# piezo-driver_v0_3-R001.net
KiCad netlist of a schematic drawn in EAGLE
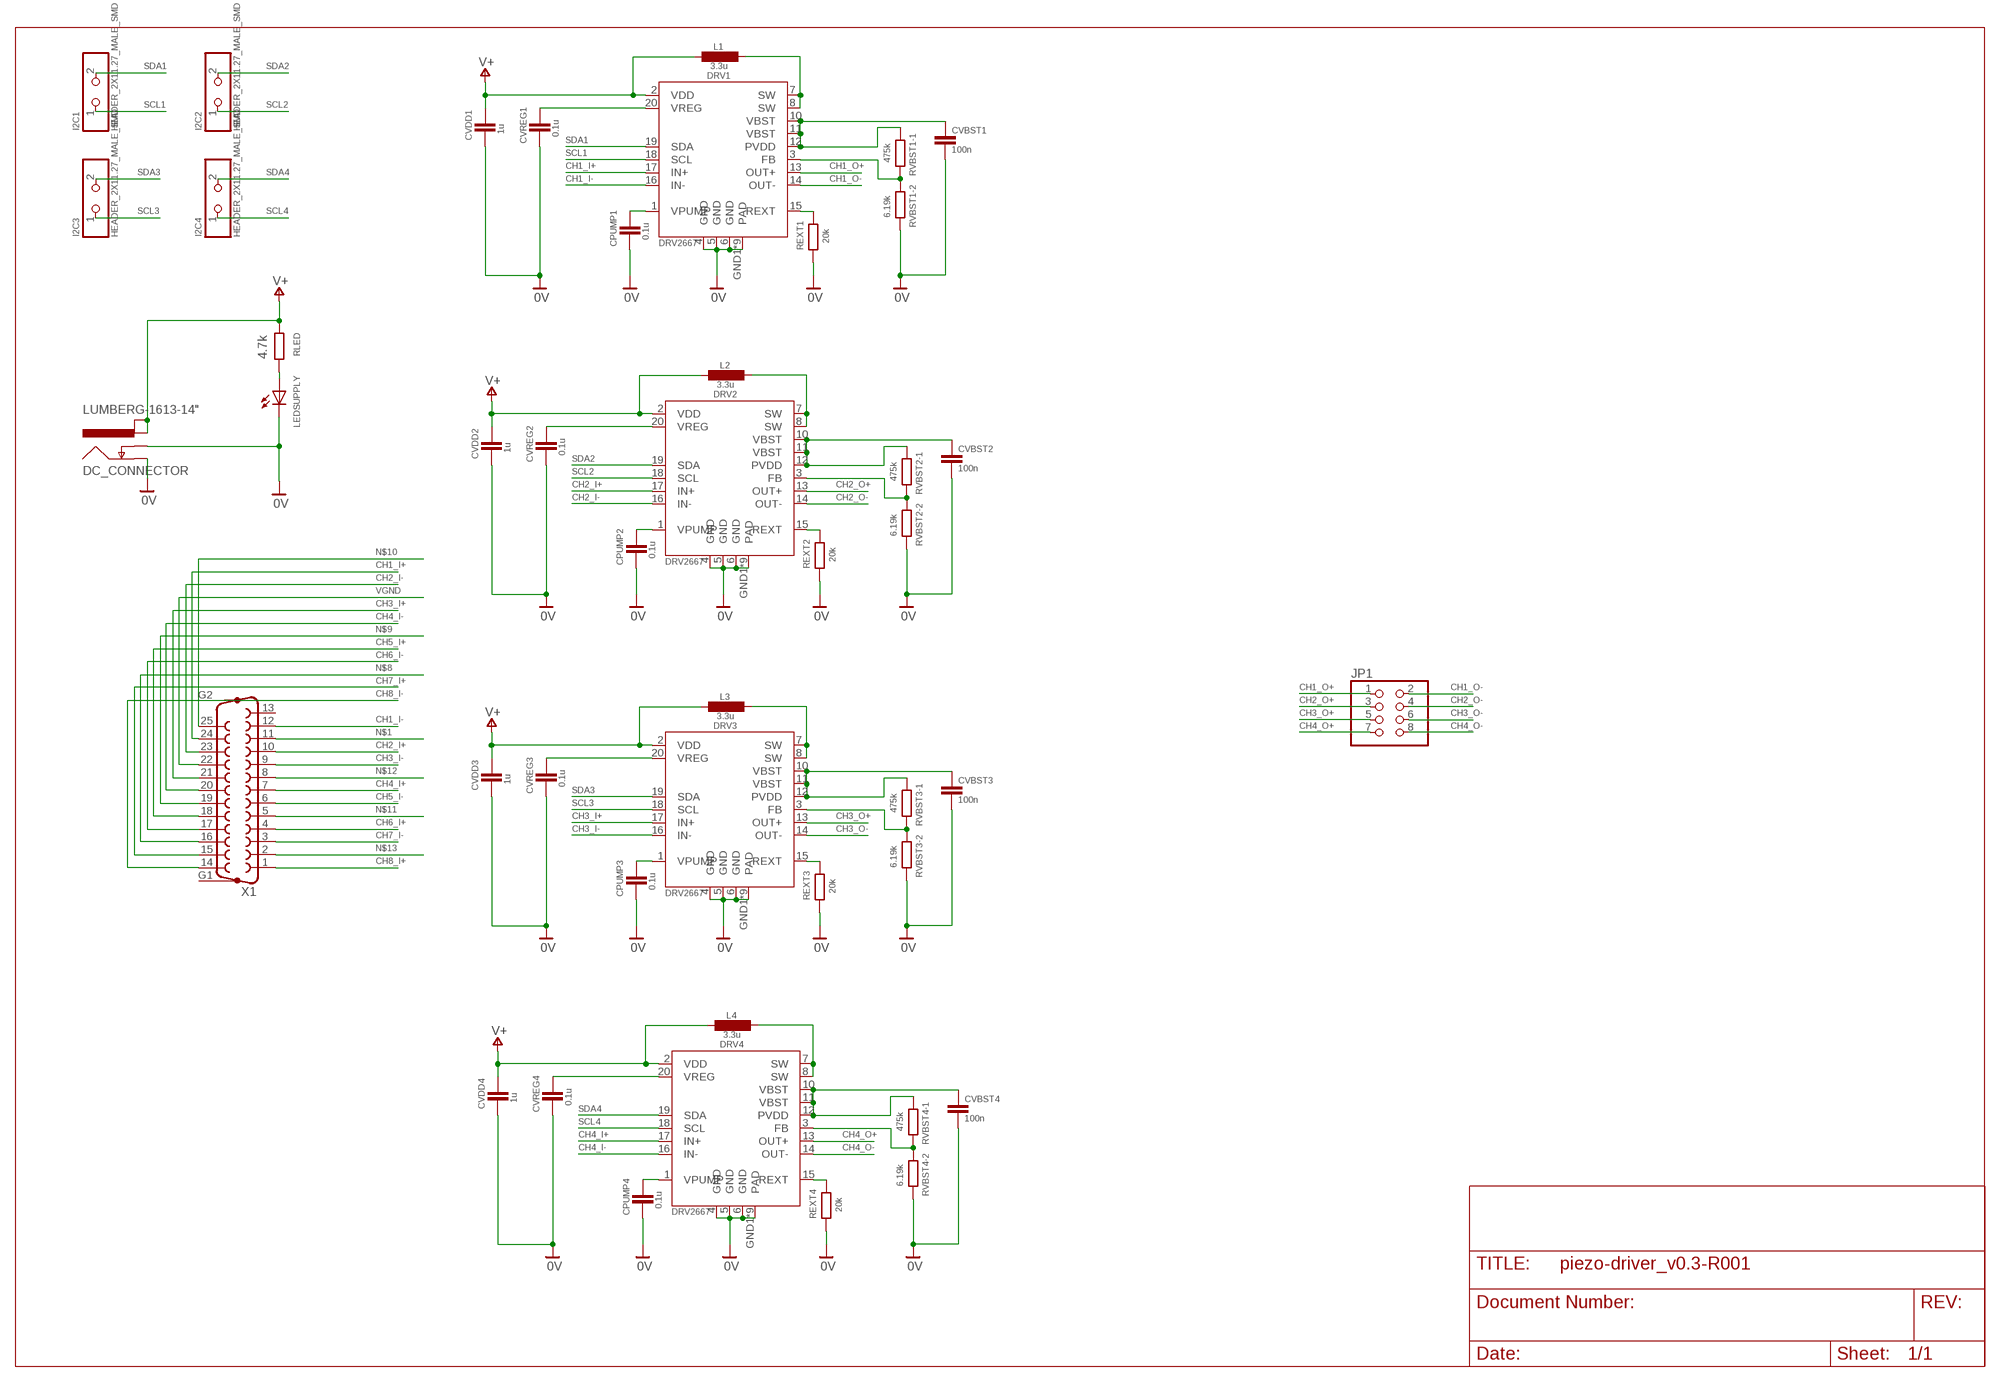
[diagram p0: schematic, sheet 1]

(export (version "E")
  (design (tool "Eeschema 10.0.6"))
  (components
    (comp (ref "CPUMP1")
      (value "0.1u")
      (footprint "eagle-import:C0805")
      (libsource (lib "eagle-import") (part "C-EUC0805"))
    )
    (comp (ref "CPUMP2")
      (value "0.1u")
      (footprint "eagle-import:C0805")
      (libsource (lib "eagle-import") (part "C-EUC0805"))
    )
    (comp (ref "CPUMP3")
      (value "0.1u")
      (footprint "eagle-import:C0805")
      (libsource (lib "eagle-import") (part "C-EUC0805"))
    )
    (comp (ref "CPUMP4")
      (value "0.1u")
      (footprint "eagle-import:C0805")
      (libsource (lib "eagle-import") (part "C-EUC0805"))
    )
    (comp (ref "CVBST1")
      (value "100n")
      (footprint "eagle-import:C0805")
      (libsource (lib "eagle-import") (part "C-EUC0805"))
    )
    (comp (ref "CVBST2")
      (value "100n")
      (footprint "eagle-import:C0805")
      (libsource (lib "eagle-import") (part "C-EUC0805"))
    )
    (comp (ref "CVBST3")
      (value "100n")
      (footprint "eagle-import:C0805")
      (libsource (lib "eagle-import") (part "C-EUC0805"))
    )
    (comp (ref "CVBST4")
      (value "100n")
      (footprint "eagle-import:C0805")
      (libsource (lib "eagle-import") (part "C-EUC0805"))
    )
    (comp (ref "CVDD1")
      (value "1u")
      (footprint "eagle-import:C0805")
      (libsource (lib "eagle-import") (part "C-EUC0805"))
    )
    (comp (ref "CVDD2")
      (value "1u")
      (footprint "eagle-import:C0805")
      (libsource (lib "eagle-import") (part "C-EUC0805"))
    )
    (comp (ref "CVDD3")
      (value "1u")
      (footprint "eagle-import:C0805")
      (libsource (lib "eagle-import") (part "C-EUC0805"))
    )
    (comp (ref "CVDD4")
      (value "1u")
      (footprint "eagle-import:C0805")
      (libsource (lib "eagle-import") (part "C-EUC0805"))
    )
    (comp (ref "CVREG1")
      (value "0.1u")
      (footprint "eagle-import:C0805")
      (libsource (lib "eagle-import") (part "C-EUC0805"))
    )
    (comp (ref "CVREG2")
      (value "0.1u")
      (footprint "eagle-import:C0805")
      (libsource (lib "eagle-import") (part "C-EUC0805"))
    )
    (comp (ref "CVREG3")
      (value "0.1u")
      (footprint "eagle-import:C0805")
      (libsource (lib "eagle-import") (part "C-EUC0805"))
    )
    (comp (ref "CVREG4")
      (value "0.1u")
      (footprint "eagle-import:C0805")
      (libsource (lib "eagle-import") (part "C-EUC0805"))
    )
    (comp (ref "DC_CONNECTOR")
      (value "LUMBERG-1613-14\"")
      (footprint "eagle-import:LUMBERG-1613_14")
      (libsource (lib "eagle-import") (part "LUMBERG-1613-14{dblquote}"))
    )
    (comp (ref "DRV1")
      (value "DRV2667QFN")
      (footprint "eagle-import:QFN400X400")
      (libsource (lib "eagle-import") (part "DRV2667QFN"))
    )
    (comp (ref "DRV2")
      (value "DRV2667QFN")
      (footprint "eagle-import:QFN400X400")
      (libsource (lib "eagle-import") (part "DRV2667QFN"))
    )
    (comp (ref "DRV3")
      (value "DRV2667QFN")
      (footprint "eagle-import:QFN400X400")
      (libsource (lib "eagle-import") (part "DRV2667QFN"))
    )
    (comp (ref "DRV4")
      (value "DRV2667QFN")
      (footprint "eagle-import:QFN400X400")
      (libsource (lib "eagle-import") (part "DRV2667QFN"))
    )
    (comp (ref "I2C1")
      (value "HEADER_2X11.27_MALE_SMD")
      (footprint "eagle-import:2X01_1.27_SMD")
      (libsource (lib "eagle-import") (part "HEADER_2X11.27_MALE_SMD"))
    )
    (comp (ref "I2C2")
      (value "HEADER_2X11.27_MALE_SMD")
      (footprint "eagle-import:2X01_1.27_SMD")
      (libsource (lib "eagle-import") (part "HEADER_2X11.27_MALE_SMD"))
    )
    (comp (ref "I2C3")
      (value "HEADER_2X11.27_MALE_SMD")
      (footprint "eagle-import:2X01_1.27_SMD")
      (libsource (lib "eagle-import") (part "HEADER_2X11.27_MALE_SMD"))
    )
    (comp (ref "I2C4")
      (value "HEADER_2X11.27_MALE_SMD")
      (footprint "eagle-import:2X01_1.27_SMD")
      (libsource (lib "eagle-import") (part "HEADER_2X11.27_MALE_SMD"))
    )
    (comp (ref "JP1")
      (value "PINHD-2X4/90")
      (footprint "eagle-import:2X04_90")
      (libsource (lib "eagle-import") (part "PINHD-2X4/90"))
    )
    (comp (ref "L1")
      (value "3.3u")
      (footprint "eagle-import:L3225M")
      (libsource (lib "eagle-import") (part "L-EUL3225M"))
    )
    (comp (ref "L2")
      (value "3.3u")
      (footprint "eagle-import:L3225M")
      (libsource (lib "eagle-import") (part "L-EUL3225M"))
    )
    (comp (ref "L3")
      (value "3.3u")
      (footprint "eagle-import:L3225M")
      (libsource (lib "eagle-import") (part "L-EUL3225M"))
    )
    (comp (ref "L4")
      (value "3.3u")
      (footprint "eagle-import:L3225M")
      (libsource (lib "eagle-import") (part "L-EUL3225M"))
    )
    (comp (ref "LEDSUPPLY")
      (value "LED0603")
      (footprint "eagle-import:LED-0603")
      (libsource (lib "eagle-import") (part "LED0603"))
    )
    (comp (ref "REXT1")
      (value "20k")
      (footprint "eagle-import:R0805")
      (libsource (lib "eagle-import") (part "R-EU_R0805"))
    )
    (comp (ref "REXT2")
      (value "20k")
      (footprint "eagle-import:R0805")
      (libsource (lib "eagle-import") (part "R-EU_R0805"))
    )
    (comp (ref "REXT3")
      (value "20k")
      (footprint "eagle-import:R0805")
      (libsource (lib "eagle-import") (part "R-EU_R0805"))
    )
    (comp (ref "REXT4")
      (value "20k")
      (footprint "eagle-import:R0805")
      (libsource (lib "eagle-import") (part "R-EU_R0805"))
    )
    (comp (ref "RLED")
      (value "4.7k")
      (footprint "eagle-import:R0805")
      (libsource (lib "eagle-import") (part "rcl_R-EU_R0805"))
    )
    (comp (ref "RVBST1-1")
      (value "475k")
      (footprint "eagle-import:R0805")
      (libsource (lib "eagle-import") (part "R-EU_R0805"))
    )
    (comp (ref "RVBST1-2")
      (value "6.19k")
      (footprint "eagle-import:R0805")
      (libsource (lib "eagle-import") (part "R-EU_R0805"))
    )
    (comp (ref "RVBST2-1")
      (value "475k")
      (footprint "eagle-import:R0805")
      (libsource (lib "eagle-import") (part "R-EU_R0805"))
    )
    (comp (ref "RVBST2-2")
      (value "6.19k")
      (footprint "eagle-import:R0805")
      (libsource (lib "eagle-import") (part "R-EU_R0805"))
    )
    (comp (ref "RVBST3-1")
      (value "475k")
      (footprint "eagle-import:R0805")
      (libsource (lib "eagle-import") (part "R-EU_R0805"))
    )
    (comp (ref "RVBST3-2")
      (value "6.19k")
      (footprint "eagle-import:R0805")
      (libsource (lib "eagle-import") (part "R-EU_R0805"))
    )
    (comp (ref "RVBST4-1")
      (value "475k")
      (footprint "eagle-import:R0805")
      (libsource (lib "eagle-import") (part "R-EU_R0805"))
    )
    (comp (ref "RVBST4-2")
      (value "6.19k")
      (footprint "eagle-import:R0805")
      (libsource (lib "eagle-import") (part "R-EU_R0805"))
    )
    (comp (ref "X1")
      (value "F25HP")
      (footprint "eagle-import:F25HP")
      (libsource (lib "eagle-import") (part "F25HP"))
    )
  )
  (nets
    (net (code "1") (name "/CH1_I+") (class "Default")
      (node (ref "DRV1") (pin "17") (pinfunction "IN+_17") (pintype "bidirectional"))
      (node (ref "X1") (pin "24") (pinfunction "24_24") (pintype "passive"))
    )
    (net (code "2") (name "/CH1_I-") (class "Default")
      (node (ref "DRV1") (pin "16") (pinfunction "IN-_16") (pintype "bidirectional"))
      (node (ref "X1") (pin "12") (pinfunction "12_12") (pintype "passive"))
    )
    (net (code "3") (name "/CH1_O+") (class "Default")
      (node (ref "DRV1") (pin "13") (pinfunction "OUT+_13") (pintype "bidirectional"))
      (node (ref "JP1") (pin "1") (pinfunction "1_1") (pintype "passive"))
    )
    (net (code "4") (name "/CH1_O-") (class "Default")
      (node (ref "DRV1") (pin "14") (pinfunction "OUT-_14") (pintype "bidirectional"))
      (node (ref "JP1") (pin "2") (pinfunction "2_2") (pintype "passive"))
    )
    (net (code "5") (name "/CH2_I+") (class "Default")
      (node (ref "DRV2") (pin "17") (pinfunction "IN+_17") (pintype "bidirectional"))
      (node (ref "X1") (pin "10") (pinfunction "10_10") (pintype "passive"))
    )
    (net (code "6") (name "/CH2_I-") (class "Default")
      (node (ref "DRV2") (pin "16") (pinfunction "IN-_16") (pintype "bidirectional"))
      (node (ref "X1") (pin "23") (pinfunction "23_23") (pintype "passive"))
    )
    (net (code "7") (name "/CH2_O+") (class "Default")
      (node (ref "DRV2") (pin "13") (pinfunction "OUT+_13") (pintype "bidirectional"))
      (node (ref "JP1") (pin "3") (pinfunction "3_3") (pintype "passive"))
    )
    (net (code "8") (name "/CH2_O-") (class "Default")
      (node (ref "DRV2") (pin "14") (pinfunction "OUT-_14") (pintype "bidirectional"))
      (node (ref "JP1") (pin "4") (pinfunction "4_4") (pintype "passive"))
    )
    (net (code "9") (name "/CH3_I+") (class "Default")
      (node (ref "DRV3") (pin "17") (pinfunction "IN+_17") (pintype "bidirectional"))
      (node (ref "X1") (pin "21") (pinfunction "21_21") (pintype "passive"))
    )
    (net (code "10") (name "/CH3_I-") (class "Default")
      (node (ref "DRV3") (pin "16") (pinfunction "IN-_16") (pintype "bidirectional"))
      (node (ref "X1") (pin "9") (pinfunction "9_9") (pintype "passive"))
    )
    (net (code "11") (name "/CH3_O+") (class "Default")
      (node (ref "DRV3") (pin "13") (pinfunction "OUT+_13") (pintype "bidirectional"))
      (node (ref "JP1") (pin "5") (pinfunction "5_5") (pintype "passive"))
    )
    (net (code "12") (name "/CH3_O-") (class "Default")
      (node (ref "DRV3") (pin "14") (pinfunction "OUT-_14") (pintype "bidirectional"))
      (node (ref "JP1") (pin "6") (pinfunction "6_6") (pintype "passive"))
    )
    (net (code "13") (name "/CH4_I+") (class "Default")
      (node (ref "DRV4") (pin "17") (pinfunction "IN+_17") (pintype "bidirectional"))
      (node (ref "X1") (pin "7") (pinfunction "7_7") (pintype "passive"))
    )
    (net (code "14") (name "/CH4_I-") (class "Default")
      (node (ref "DRV4") (pin "16") (pinfunction "IN-_16") (pintype "bidirectional"))
      (node (ref "X1") (pin "20") (pinfunction "20_20") (pintype "passive"))
    )
    (net (code "15") (name "/CH4_O+") (class "Default")
      (node (ref "DRV4") (pin "13") (pinfunction "OUT+_13") (pintype "bidirectional"))
      (node (ref "JP1") (pin "7") (pinfunction "7_7") (pintype "passive"))
    )
    (net (code "16") (name "/CH4_O-") (class "Default")
      (node (ref "DRV4") (pin "14") (pinfunction "OUT-_14") (pintype "bidirectional"))
      (node (ref "JP1") (pin "8") (pinfunction "8_8") (pintype "passive"))
    )
    (net (code "17") (name "/CH5_I+") (class "Default")
      (node (ref "X1") (pin "18") (pinfunction "18_18") (pintype "passive"))
    )
    (net (code "18") (name "/CH5_I-") (class "Default")
      (node (ref "X1") (pin "6") (pinfunction "6_6") (pintype "passive"))
    )
    (net (code "19") (name "/CH6_I+") (class "Default")
      (node (ref "X1") (pin "4") (pinfunction "4_4") (pintype "passive"))
    )
    (net (code "20") (name "/CH6_I-") (class "Default")
      (node (ref "X1") (pin "17") (pinfunction "17_17") (pintype "passive"))
    )
    (net (code "21") (name "/CH7_I+") (class "Default")
      (node (ref "X1") (pin "15") (pinfunction "15_15") (pintype "passive"))
    )
    (net (code "22") (name "/CH7_I-") (class "Default")
      (node (ref "X1") (pin "3") (pinfunction "3_3") (pintype "passive"))
    )
    (net (code "23") (name "/CH8_I+") (class "Default")
      (node (ref "X1") (pin "1") (pinfunction "1_1") (pintype "passive"))
    )
    (net (code "24") (name "/CH8_I-") (class "Default")
      (node (ref "X1") (pin "14") (pinfunction "14_14") (pintype "passive"))
    )
    (net (code "25") (name "/N$1") (class "Default")
      (node (ref "X1") (pin "11") (pinfunction "11_11") (pintype "passive"))
    )
    (net (code "26") (name "/N$8") (class "Default")
      (node (ref "X1") (pin "16") (pinfunction "16_16") (pintype "passive"))
    )
    (net (code "27") (name "/N$9") (class "Default")
      (node (ref "X1") (pin "19") (pinfunction "19_19") (pintype "passive"))
    )
    (net (code "28") (name "/N$10") (class "Default")
      (node (ref "X1") (pin "25") (pinfunction "25_25") (pintype "passive"))
    )
    (net (code "29") (name "/N$11") (class "Default")
      (node (ref "X1") (pin "5") (pinfunction "5_5") (pintype "passive"))
    )
    (net (code "30") (name "/N$12") (class "Default")
      (node (ref "X1") (pin "8") (pinfunction "8_8") (pintype "passive"))
    )
    (net (code "31") (name "/N$13") (class "Default")
      (node (ref "X1") (pin "2") (pinfunction "2_2") (pintype "passive"))
    )
    (net (code "32") (name "/SCL1") (class "Default")
      (node (ref "DRV1") (pin "18") (pinfunction "SCL_18") (pintype "bidirectional"))
      (node (ref "I2C1") (pin "1") (pinfunction "1_1") (pintype "passive"))
    )
    (net (code "33") (name "/SCL2") (class "Default")
      (node (ref "DRV2") (pin "18") (pinfunction "SCL_18") (pintype "bidirectional"))
      (node (ref "I2C2") (pin "1") (pinfunction "1_1") (pintype "passive"))
    )
    (net (code "34") (name "/SCL3") (class "Default")
      (node (ref "DRV3") (pin "18") (pinfunction "SCL_18") (pintype "bidirectional"))
      (node (ref "I2C3") (pin "1") (pinfunction "1_1") (pintype "passive"))
    )
    (net (code "35") (name "/SCL4") (class "Default")
      (node (ref "DRV4") (pin "18") (pinfunction "SCL_18") (pintype "bidirectional"))
      (node (ref "I2C4") (pin "1") (pinfunction "1_1") (pintype "passive"))
    )
    (net (code "36") (name "/SDA1") (class "Default")
      (node (ref "DRV1") (pin "19") (pinfunction "SDA_19") (pintype "bidirectional"))
      (node (ref "I2C1") (pin "2") (pinfunction "2_2") (pintype "passive"))
    )
    (net (code "37") (name "/SDA2") (class "Default")
      (node (ref "DRV2") (pin "19") (pinfunction "SDA_19") (pintype "bidirectional"))
      (node (ref "I2C2") (pin "2") (pinfunction "2_2") (pintype "passive"))
    )
    (net (code "38") (name "/SDA3") (class "Default")
      (node (ref "DRV3") (pin "19") (pinfunction "SDA_19") (pintype "bidirectional"))
      (node (ref "I2C3") (pin "2") (pinfunction "2_2") (pintype "passive"))
    )
    (net (code "39") (name "/SDA4") (class "Default")
      (node (ref "DRV4") (pin "19") (pinfunction "SDA_19") (pintype "bidirectional"))
      (node (ref "I2C4") (pin "2") (pinfunction "2_2") (pintype "passive"))
    )
    (net (code "40") (name "/VGND") (class "Default")
      (node (ref "X1") (pin "22") (pinfunction "22_22") (pintype "passive"))
    )
    (net (code "41") (name "0V") (class "Default")
      (node (ref "CPUMP1") (pin "2") (pinfunction "2_2") (pintype "passive"))
      (node (ref "CPUMP2") (pin "2") (pinfunction "2_2") (pintype "passive"))
      (node (ref "CPUMP3") (pin "2") (pinfunction "2_2") (pintype "passive"))
      (node (ref "CPUMP4") (pin "2") (pinfunction "2_2") (pintype "passive"))
      (node (ref "CVBST1") (pin "2") (pinfunction "2_2") (pintype "passive"))
      (node (ref "CVBST2") (pin "2") (pinfunction "2_2") (pintype "passive"))
      (node (ref "CVBST3") (pin "2") (pinfunction "2_2") (pintype "passive"))
      (node (ref "CVBST4") (pin "2") (pinfunction "2_2") (pintype "passive"))
      (node (ref "CVDD1") (pin "2") (pinfunction "2_2") (pintype "passive"))
      (node (ref "CVDD2") (pin "2") (pinfunction "2_2") (pintype "passive"))
      (node (ref "CVDD3") (pin "2") (pinfunction "2_2") (pintype "passive"))
      (node (ref "CVDD4") (pin "2") (pinfunction "2_2") (pintype "passive"))
      (node (ref "CVREG1") (pin "2") (pinfunction "2_2") (pintype "passive"))
      (node (ref "CVREG2") (pin "2") (pinfunction "2_2") (pintype "passive"))
      (node (ref "CVREG3") (pin "2") (pinfunction "2_2") (pintype "passive"))
      (node (ref "CVREG4") (pin "2") (pinfunction "2_2") (pintype "passive"))
      (node (ref "DC_CONNECTOR") (pin "1") (pinfunction "GND_1") (pintype "power_in"))
      (node (ref "DC_CONNECTOR") (pin "2") (pinfunction "GND_INS_2") (pintype "power_in"))
      (node (ref "DRV1") (pin "4") (pinfunction "GND_4") (pintype "bidirectional"))
      (node (ref "DRV1") (pin "5") (pinfunction "GND_5") (pintype "bidirectional"))
      (node (ref "DRV1") (pin "6") (pinfunction "GND_6") (pintype "bidirectional"))
      (node (ref "DRV1") (pin "GND1") (pinfunction "PAD_GND1") (pintype "bidirectional"))
      (node (ref "DRV1") (pin "GND2") (pinfunction "PAD_GND2") (pintype "bidirectional"))
      (node (ref "DRV1") (pin "GND3") (pinfunction "PAD_GND3") (pintype "bidirectional"))
      (node (ref "DRV1") (pin "GND4") (pinfunction "PAD_GND4") (pintype "bidirectional"))
      (node (ref "DRV1") (pin "GND5") (pinfunction "PAD_GND5") (pintype "bidirectional"))
      (node (ref "DRV1") (pin "GND6") (pinfunction "PAD_GND6") (pintype "bidirectional"))
      (node (ref "DRV1") (pin "GND7") (pinfunction "PAD_GND7") (pintype "bidirectional"))
      (node (ref "DRV1") (pin "GND8") (pinfunction "PAD_GND8") (pintype "bidirectional"))
      (node (ref "DRV1") (pin "GND9") (pinfunction "PAD_GND9") (pintype "bidirectional"))
      (node (ref "DRV2") (pin "4") (pinfunction "GND_4") (pintype "bidirectional"))
      (node (ref "DRV2") (pin "5") (pinfunction "GND_5") (pintype "bidirectional"))
      (node (ref "DRV2") (pin "6") (pinfunction "GND_6") (pintype "bidirectional"))
      (node (ref "DRV2") (pin "GND1") (pinfunction "PAD_GND1") (pintype "bidirectional"))
      (node (ref "DRV2") (pin "GND2") (pinfunction "PAD_GND2") (pintype "bidirectional"))
      (node (ref "DRV2") (pin "GND3") (pinfunction "PAD_GND3") (pintype "bidirectional"))
      (node (ref "DRV2") (pin "GND4") (pinfunction "PAD_GND4") (pintype "bidirectional"))
      (node (ref "DRV2") (pin "GND5") (pinfunction "PAD_GND5") (pintype "bidirectional"))
      (node (ref "DRV2") (pin "GND6") (pinfunction "PAD_GND6") (pintype "bidirectional"))
      (node (ref "DRV2") (pin "GND7") (pinfunction "PAD_GND7") (pintype "bidirectional"))
      (node (ref "DRV2") (pin "GND8") (pinfunction "PAD_GND8") (pintype "bidirectional"))
      (node (ref "DRV2") (pin "GND9") (pinfunction "PAD_GND9") (pintype "bidirectional"))
      (node (ref "DRV3") (pin "4") (pinfunction "GND_4") (pintype "bidirectional"))
      (node (ref "DRV3") (pin "5") (pinfunction "GND_5") (pintype "bidirectional"))
      (node (ref "DRV3") (pin "6") (pinfunction "GND_6") (pintype "bidirectional"))
      (node (ref "DRV3") (pin "GND1") (pinfunction "PAD_GND1") (pintype "bidirectional"))
      (node (ref "DRV3") (pin "GND2") (pinfunction "PAD_GND2") (pintype "bidirectional"))
      (node (ref "DRV3") (pin "GND3") (pinfunction "PAD_GND3") (pintype "bidirectional"))
      (node (ref "DRV3") (pin "GND4") (pinfunction "PAD_GND4") (pintype "bidirectional"))
      (node (ref "DRV3") (pin "GND5") (pinfunction "PAD_GND5") (pintype "bidirectional"))
      (node (ref "DRV3") (pin "GND6") (pinfunction "PAD_GND6") (pintype "bidirectional"))
      (node (ref "DRV3") (pin "GND7") (pinfunction "PAD_GND7") (pintype "bidirectional"))
      (node (ref "DRV3") (pin "GND8") (pinfunction "PAD_GND8") (pintype "bidirectional"))
      (node (ref "DRV3") (pin "GND9") (pinfunction "PAD_GND9") (pintype "bidirectional"))
      (node (ref "DRV4") (pin "4") (pinfunction "GND_4") (pintype "bidirectional"))
      (node (ref "DRV4") (pin "5") (pinfunction "GND_5") (pintype "bidirectional"))
      (node (ref "DRV4") (pin "6") (pinfunction "GND_6") (pintype "bidirectional"))
      (node (ref "DRV4") (pin "GND1") (pinfunction "PAD_GND1") (pintype "bidirectional"))
      (node (ref "DRV4") (pin "GND2") (pinfunction "PAD_GND2") (pintype "bidirectional"))
      (node (ref "DRV4") (pin "GND3") (pinfunction "PAD_GND3") (pintype "bidirectional"))
      (node (ref "DRV4") (pin "GND4") (pinfunction "PAD_GND4") (pintype "bidirectional"))
      (node (ref "DRV4") (pin "GND5") (pinfunction "PAD_GND5") (pintype "bidirectional"))
      (node (ref "DRV4") (pin "GND6") (pinfunction "PAD_GND6") (pintype "bidirectional"))
      (node (ref "DRV4") (pin "GND7") (pinfunction "PAD_GND7") (pintype "bidirectional"))
      (node (ref "DRV4") (pin "GND8") (pinfunction "PAD_GND8") (pintype "bidirectional"))
      (node (ref "DRV4") (pin "GND9") (pinfunction "PAD_GND9") (pintype "bidirectional"))
      (node (ref "LEDSUPPLY") (pin "C") (pinfunction "C_C") (pintype "passive"))
      (node (ref "REXT1") (pin "1") (pinfunction "1_1") (pintype "passive"))
      (node (ref "REXT2") (pin "1") (pinfunction "1_1") (pintype "passive"))
      (node (ref "REXT3") (pin "1") (pinfunction "1_1") (pintype "passive"))
      (node (ref "REXT4") (pin "1") (pinfunction "1_1") (pintype "passive"))
      (node (ref "RVBST1-2") (pin "1") (pinfunction "1_1") (pintype "passive"))
      (node (ref "RVBST2-2") (pin "1") (pinfunction "1_1") (pintype "passive"))
      (node (ref "RVBST3-2") (pin "1") (pinfunction "1_1") (pintype "passive"))
      (node (ref "RVBST4-2") (pin "1") (pinfunction "1_1") (pintype "passive"))
    )
    (net (code "42") (name "Net-(DRV1-FB)") (class "Default")
      (node (ref "DRV1") (pin "3") (pinfunction "FB_3") (pintype "bidirectional"))
      (node (ref "RVBST1-1") (pin "1") (pinfunction "1_1") (pintype "passive"))
      (node (ref "RVBST1-2") (pin "2") (pinfunction "2_2") (pintype "passive"))
    )
    (net (code "43") (name "Net-(DRV1-PVDD)") (class "Default")
      (node (ref "CVBST1") (pin "1") (pinfunction "1_1") (pintype "passive"))
      (node (ref "DRV1") (pin "10") (pinfunction "VBST_10") (pintype "bidirectional"))
      (node (ref "DRV1") (pin "11") (pinfunction "VBST_11") (pintype "bidirectional"))
      (node (ref "DRV1") (pin "12") (pinfunction "PVDD_12") (pintype "bidirectional"))
      (node (ref "RVBST1-1") (pin "2") (pinfunction "2_2") (pintype "passive"))
    )
    (net (code "44") (name "Net-(DRV1-REXT)") (class "Default")
      (node (ref "DRV1") (pin "15") (pinfunction "REXT_15") (pintype "bidirectional"))
      (node (ref "REXT1") (pin "2") (pinfunction "2_2") (pintype "passive"))
    )
    (net (code "45") (name "Net-(DRV1-SW-Pad7)") (class "Default")
      (node (ref "DRV1") (pin "7") (pinfunction "SW_7") (pintype "bidirectional"))
      (node (ref "DRV1") (pin "8") (pinfunction "SW_8") (pintype "bidirectional"))
      (node (ref "L1") (pin "1") (pinfunction "1_1") (pintype "passive"))
    )
    (net (code "46") (name "Net-(DRV1-VPUMP)") (class "Default")
      (node (ref "CPUMP1") (pin "1") (pinfunction "1_1") (pintype "passive"))
      (node (ref "DRV1") (pin "1") (pinfunction "VPUMP_1") (pintype "bidirectional"))
    )
    (net (code "47") (name "Net-(DRV1-VREG)") (class "Default")
      (node (ref "CVREG1") (pin "1") (pinfunction "1_1") (pintype "passive"))
      (node (ref "DRV1") (pin "20") (pinfunction "VREG_20") (pintype "bidirectional"))
    )
    (net (code "48") (name "Net-(DRV2-FB)") (class "Default")
      (node (ref "DRV2") (pin "3") (pinfunction "FB_3") (pintype "bidirectional"))
      (node (ref "RVBST2-1") (pin "1") (pinfunction "1_1") (pintype "passive"))
      (node (ref "RVBST2-2") (pin "2") (pinfunction "2_2") (pintype "passive"))
    )
    (net (code "49") (name "Net-(DRV2-PVDD)") (class "Default")
      (node (ref "CVBST2") (pin "1") (pinfunction "1_1") (pintype "passive"))
      (node (ref "DRV2") (pin "10") (pinfunction "VBST_10") (pintype "bidirectional"))
      (node (ref "DRV2") (pin "11") (pinfunction "VBST_11") (pintype "bidirectional"))
      (node (ref "DRV2") (pin "12") (pinfunction "PVDD_12") (pintype "bidirectional"))
      (node (ref "RVBST2-1") (pin "2") (pinfunction "2_2") (pintype "passive"))
    )
    (net (code "50") (name "Net-(DRV2-REXT)") (class "Default")
      (node (ref "DRV2") (pin "15") (pinfunction "REXT_15") (pintype "bidirectional"))
      (node (ref "REXT2") (pin "2") (pinfunction "2_2") (pintype "passive"))
    )
    (net (code "51") (name "Net-(DRV2-SW-Pad7)") (class "Default")
      (node (ref "DRV2") (pin "7") (pinfunction "SW_7") (pintype "bidirectional"))
      (node (ref "DRV2") (pin "8") (pinfunction "SW_8") (pintype "bidirectional"))
      (node (ref "L2") (pin "1") (pinfunction "1_1") (pintype "passive"))
    )
    (net (code "52") (name "Net-(DRV2-VPUMP)") (class "Default")
      (node (ref "CPUMP2") (pin "1") (pinfunction "1_1") (pintype "passive"))
      (node (ref "DRV2") (pin "1") (pinfunction "VPUMP_1") (pintype "bidirectional"))
    )
    (net (code "53") (name "Net-(DRV2-VREG)") (class "Default")
      (node (ref "CVREG2") (pin "1") (pinfunction "1_1") (pintype "passive"))
      (node (ref "DRV2") (pin "20") (pinfunction "VREG_20") (pintype "bidirectional"))
    )
    (net (code "54") (name "Net-(DRV3-FB)") (class "Default")
      (node (ref "DRV3") (pin "3") (pinfunction "FB_3") (pintype "bidirectional"))
      (node (ref "RVBST3-1") (pin "1") (pinfunction "1_1") (pintype "passive"))
      (node (ref "RVBST3-2") (pin "2") (pinfunction "2_2") (pintype "passive"))
    )
    (net (code "55") (name "Net-(DRV3-PVDD)") (class "Default")
      (node (ref "CVBST3") (pin "1") (pinfunction "1_1") (pintype "passive"))
      (node (ref "DRV3") (pin "10") (pinfunction "VBST_10") (pintype "bidirectional"))
      (node (ref "DRV3") (pin "11") (pinfunction "VBST_11") (pintype "bidirectional"))
      (node (ref "DRV3") (pin "12") (pinfunction "PVDD_12") (pintype "bidirectional"))
      (node (ref "RVBST3-1") (pin "2") (pinfunction "2_2") (pintype "passive"))
    )
    (net (code "56") (name "Net-(DRV3-REXT)") (class "Default")
      (node (ref "DRV3") (pin "15") (pinfunction "REXT_15") (pintype "bidirectional"))
      (node (ref "REXT3") (pin "2") (pinfunction "2_2") (pintype "passive"))
    )
    (net (code "57") (name "Net-(DRV3-SW-Pad7)") (class "Default")
      (node (ref "DRV3") (pin "7") (pinfunction "SW_7") (pintype "bidirectional"))
      (node (ref "DRV3") (pin "8") (pinfunction "SW_8") (pintype "bidirectional"))
      (node (ref "L3") (pin "1") (pinfunction "1_1") (pintype "passive"))
    )
    (net (code "58") (name "Net-(DRV3-VPUMP)") (class "Default")
      (node (ref "CPUMP3") (pin "1") (pinfunction "1_1") (pintype "passive"))
      (node (ref "DRV3") (pin "1") (pinfunction "VPUMP_1") (pintype "bidirectional"))
    )
    (net (code "59") (name "Net-(DRV3-VREG)") (class "Default")
      (node (ref "CVREG3") (pin "1") (pinfunction "1_1") (pintype "passive"))
      (node (ref "DRV3") (pin "20") (pinfunction "VREG_20") (pintype "bidirectional"))
    )
    (net (code "60") (name "Net-(DRV4-FB)") (class "Default")
      (node (ref "DRV4") (pin "3") (pinfunction "FB_3") (pintype "bidirectional"))
      (node (ref "RVBST4-1") (pin "1") (pinfunction "1_1") (pintype "passive"))
      (node (ref "RVBST4-2") (pin "2") (pinfunction "2_2") (pintype "passive"))
    )
    (net (code "61") (name "Net-(DRV4-PVDD)") (class "Default")
      (node (ref "CVBST4") (pin "1") (pinfunction "1_1") (pintype "passive"))
      (node (ref "DRV4") (pin "10") (pinfunction "VBST_10") (pintype "bidirectional"))
      (node (ref "DRV4") (pin "11") (pinfunction "VBST_11") (pintype "bidirectional"))
      (node (ref "DRV4") (pin "12") (pinfunction "PVDD_12") (pintype "bidirectional"))
      (node (ref "RVBST4-1") (pin "2") (pinfunction "2_2") (pintype "passive"))
    )
    (net (code "62") (name "Net-(DRV4-REXT)") (class "Default")
      (node (ref "DRV4") (pin "15") (pinfunction "REXT_15") (pintype "bidirectional"))
      (node (ref "REXT4") (pin "2") (pinfunction "2_2") (pintype "passive"))
    )
    (net (code "63") (name "Net-(DRV4-SW-Pad7)") (class "Default")
      (node (ref "DRV4") (pin "7") (pinfunction "SW_7") (pintype "bidirectional"))
      (node (ref "DRV4") (pin "8") (pinfunction "SW_8") (pintype "bidirectional"))
      (node (ref "L4") (pin "1") (pinfunction "1_1") (pintype "passive"))
    )
    (net (code "64") (name "Net-(DRV4-VPUMP)") (class "Default")
      (node (ref "CPUMP4") (pin "1") (pinfunction "1_1") (pintype "passive"))
      (node (ref "DRV4") (pin "1") (pinfunction "VPUMP_1") (pintype "bidirectional"))
    )
    (net (code "65") (name "Net-(DRV4-VREG)") (class "Default")
      (node (ref "CVREG4") (pin "1") (pinfunction "1_1") (pintype "passive"))
      (node (ref "DRV4") (pin "20") (pinfunction "VREG_20") (pintype "bidirectional"))
    )
    (net (code "66") (name "Net-(LEDSUPPLY-PadA)") (class "Default")
      (node (ref "LEDSUPPLY") (pin "A") (pinfunction "A_A") (pintype "passive"))
      (node (ref "RLED") (pin "1") (pinfunction "1_1") (pintype "passive"))
    )
    (net (code "67") (name "V+") (class "Default")
      (node (ref "CVDD1") (pin "1") (pinfunction "1_1") (pintype "passive"))
      (node (ref "CVDD2") (pin "1") (pinfunction "1_1") (pintype "passive"))
      (node (ref "CVDD3") (pin "1") (pinfunction "1_1") (pintype "passive"))
      (node (ref "CVDD4") (pin "1") (pinfunction "1_1") (pintype "passive"))
      (node (ref "DC_CONNECTOR") (pin "3") (pinfunction "PWR_1_3") (pintype "power_in"))
      (node (ref "DC_CONNECTOR") (pin "4") (pinfunction "PWR_2_4") (pintype "power_in"))
      (node (ref "DRV1") (pin "2") (pinfunction "VDD_2") (pintype "bidirectional"))
      (node (ref "DRV2") (pin "2") (pinfunction "VDD_2") (pintype "bidirectional"))
      (node (ref "DRV3") (pin "2") (pinfunction "VDD_2") (pintype "bidirectional"))
      (node (ref "DRV4") (pin "2") (pinfunction "VDD_2") (pintype "bidirectional"))
      (node (ref "L1") (pin "2") (pinfunction "2_2") (pintype "passive"))
      (node (ref "L2") (pin "2") (pinfunction "2_2") (pintype "passive"))
      (node (ref "L3") (pin "2") (pinfunction "2_2") (pintype "passive"))
      (node (ref "L4") (pin "2") (pinfunction "2_2") (pintype "passive"))
      (node (ref "RLED") (pin "2") (pinfunction "2_2") (pintype "passive"))
    )
    (net (code "68") (name "unconnected-(X1-Pad13)") (class "Default")
      (node (ref "X1") (pin "13") (pinfunction "13_13") (pintype "passive"))
    )
    (net (code "69") (name "unconnected-(X1-PadG1)") (class "Default")
      (node (ref "X1") (pin "G1") (pinfunction "G1_G1") (pintype "passive"))
    )
    (net (code "70") (name "unconnected-(X1-PadG2)") (class "Default")
      (node (ref "X1") (pin "G2") (pinfunction "G2_G2") (pintype "passive"))
    )
  )
)
